# HandheldOsc.net
KiCad netlist of a schematic drawn in EAGLE
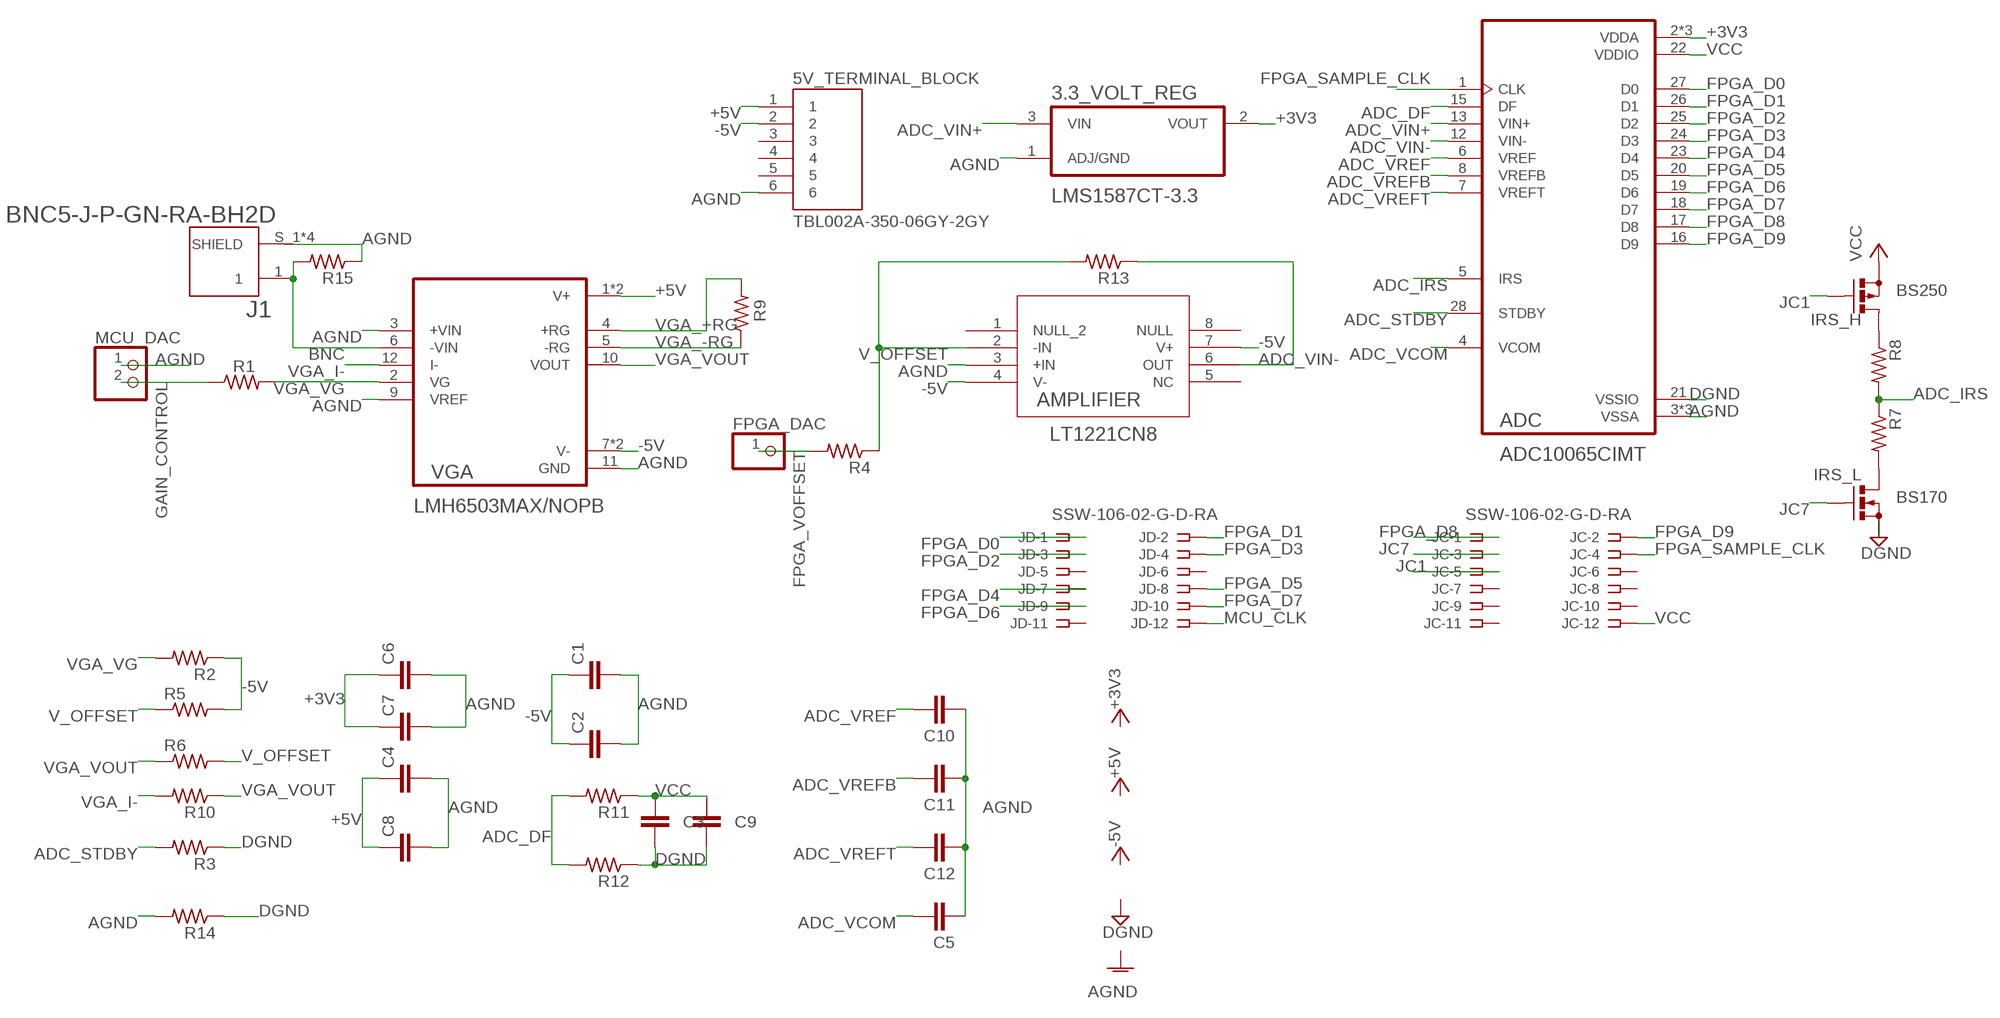
[diagram p0: schematic, sheet 1]

(export (version "E")
  (design (tool "Eeschema 10.0.6"))
  (components
    (comp (ref "3.3_VOLT_REG")
      (value "LMS1587CT-3.3")
      (footprint "eagle-import:TO254P1054X470X1955-3")
      (fields (field (name "MF") "Texas Instruments") (field (name "MP") "LMS1587CT-3.3/NOPB"))
      (libsource (lib "eagle-import") (part "LMS1587CT-3.3"))
    )
    (comp (ref "5V_TERMINAL_BLOCK")
      (value "TBL002A-350-06GY-2GY")
      (footprint "eagle-import:CUI_TBL002A-350-06GY-2GY")
      (fields (field (name "MF") "CUI Devices"))
      (libsource (lib "eagle-import") (part "TBL002A-350-06GY-2GY"))
    )
    (comp (ref "ADC")
      (value "ADC10065CIMT")
      (footprint "eagle-import:SOP65P640X120-28N")
      (fields (field (name "DIGI-KEY_PART_NUMBER") "296-35231-2-ND") (field (name "MF") "Texas Instruments"))
      (libsource (lib "eagle-import") (part "ADC10065CIMT"))
    )
    (comp (ref "AMPLIFIER")
      (value "LT1221CN8")
      (footprint "eagle-import:PDIP-8_N")
      (fields
        (field (name "DIGI-KEY_PART_NUMBER") "LT1221CN8#PBF-ND")
        (field (name "MF") "Linear Technology")
      )
      (libsource (lib "eagle-import") (part "LT1221CN8"))
    )
    (comp (ref "C1")
      (value "C2,5-3")
      (footprint "eagle-import:C2.5-3")
      (libsource (lib "eagle-import") (part "C2,5-3"))
    )
    (comp (ref "C2")
      (value "C2,5-3")
      (footprint "eagle-import:C2.5-3")
      (libsource (lib "eagle-import") (part "C2,5-3"))
    )
    (comp (ref "C3")
      (value "C2,5-3")
      (footprint "eagle-import:C2.5-3")
      (libsource (lib "eagle-import") (part "C2,5-3"))
    )
    (comp (ref "C4")
      (value "C2,5-3")
      (footprint "eagle-import:C2.5-3")
      (libsource (lib "eagle-import") (part "C2,5-3"))
    )
    (comp (ref "C5")
      (value "C2,5-3")
      (footprint "eagle-import:C2.5-3")
      (libsource (lib "eagle-import") (part "C2,5-3"))
    )
    (comp (ref "C6")
      (value "C2,5-3")
      (footprint "eagle-import:C2.5-3")
      (libsource (lib "eagle-import") (part "C2,5-3"))
    )
    (comp (ref "C7")
      (value "C2,5-3")
      (footprint "eagle-import:C2.5-3")
      (libsource (lib "eagle-import") (part "C2,5-3"))
    )
    (comp (ref "C8")
      (value "C2,5-3")
      (footprint "eagle-import:C2.5-3")
      (libsource (lib "eagle-import") (part "C2,5-3"))
    )
    (comp (ref "C9")
      (value "C2,5-3")
      (footprint "eagle-import:C2.5-3")
      (libsource (lib "eagle-import") (part "C2,5-3"))
    )
    (comp (ref "C10")
      (value "C2,5-3")
      (footprint "eagle-import:C2.5-3")
      (libsource (lib "eagle-import") (part "C2,5-3"))
    )
    (comp (ref "C11")
      (value "C2,5-3")
      (footprint "eagle-import:C2.5-3")
      (libsource (lib "eagle-import") (part "C2,5-3"))
    )
    (comp (ref "C12")
      (value "C2,5-3")
      (footprint "eagle-import:C2.5-3")
      (libsource (lib "eagle-import") (part "C2,5-3"))
    )
    (comp (ref "FPGA_DAC")
      (value "PINHD-1X1")
      (footprint "eagle-import:1X01")
      (libsource (lib "eagle-import") (part "PINHD-1X1"))
    )
    (comp (ref "IRS_H")
      (value "BS250")
      (footprint "eagle-import:SOT54E")
      (libsource (lib "eagle-import") (part "BS250"))
    )
    (comp (ref "IRS_L")
      (value "BS170")
      (footprint "eagle-import:SOT54E")
      (libsource (lib "eagle-import") (part "BS170"))
    )
    (comp (ref "J1")
      (value "BNC5-J-P-GN-RA-BH2D")
      (footprint "eagle-import:SAMTEC_BNC5-J-P-GN-RA-BH2D")
      (fields (field (name "DIGI-KEY_PART_NUMBER") "SAM9177-ND") (field (name "MF") "Samtec"))
      (libsource (lib "eagle-import") (part "BNC5-J-P-GN-RA-BH2D"))
    )
    (comp (ref "JC")
      (value "SSW-106-02-G-D-RA")
      (footprint "eagle-import:SSW-106-02-G-D-RA")
      (fields (field (name "MF") "Samtec Inc."))
      (libsource (lib "eagle-import") (part "SSW-106-02-G-D-RA"))
    )
    (comp (ref "JD")
      (value "SSW-106-02-G-D-RA")
      (footprint "eagle-import:SSW-106-02-G-D-RA")
      (fields (field (name "MF") "Samtec Inc."))
      (libsource (lib "eagle-import") (part "SSW-106-02-G-D-RA"))
    )
    (comp (ref "MCU_DAC")
      (value "PINHD-1X2")
      (footprint "eagle-import:1X02")
      (libsource (lib "eagle-import") (part "PINHD-1X2"))
    )
    (comp (ref "R1")
      (value "R-US_0207/12")
      (footprint "eagle-import:0207_12")
      (libsource (lib "eagle-import") (part "R-US_0207/12"))
    )
    (comp (ref "R2")
      (value "R-US_0207/12")
      (footprint "eagle-import:0207_12")
      (libsource (lib "eagle-import") (part "R-US_0207/12"))
    )
    (comp (ref "R3")
      (value "R-US_0207/12")
      (footprint "eagle-import:0207_12")
      (libsource (lib "eagle-import") (part "R-US_0207/12"))
    )
    (comp (ref "R4")
      (value "R-US_0207/12")
      (footprint "eagle-import:0207_12")
      (libsource (lib "eagle-import") (part "R-US_0207/12"))
    )
    (comp (ref "R5")
      (value "R-US_0207/12")
      (footprint "eagle-import:0207_12")
      (libsource (lib "eagle-import") (part "R-US_0207/12"))
    )
    (comp (ref "R6")
      (value "R-US_0207/12")
      (footprint "eagle-import:0207_12")
      (libsource (lib "eagle-import") (part "R-US_0207/12"))
    )
    (comp (ref "R7")
      (value "R-US_0207/12")
      (footprint "eagle-import:0207_12")
      (libsource (lib "eagle-import") (part "R-US_0207/12"))
    )
    (comp (ref "R8")
      (value "R-US_0207/12")
      (footprint "eagle-import:0207_12")
      (libsource (lib "eagle-import") (part "R-US_0207/12"))
    )
    (comp (ref "R9")
      (value "R-US_0207/12")
      (footprint "eagle-import:0207_12")
      (libsource (lib "eagle-import") (part "R-US_0207/12"))
    )
    (comp (ref "R10")
      (value "R-US_0207/12")
      (footprint "eagle-import:0207_12")
      (libsource (lib "eagle-import") (part "R-US_0207/12"))
    )
    (comp (ref "R11")
      (value "R-US_0207/12")
      (footprint "eagle-import:0207_12")
      (libsource (lib "eagle-import") (part "R-US_0207/12"))
    )
    (comp (ref "R12")
      (value "R-US_0207/12")
      (footprint "eagle-import:0207_12")
      (libsource (lib "eagle-import") (part "R-US_0207/12"))
    )
    (comp (ref "R13")
      (value "R-US_0207/12")
      (footprint "eagle-import:0207_12")
      (libsource (lib "eagle-import") (part "R-US_0207/12"))
    )
    (comp (ref "R14")
      (value "R-US_0207/12")
      (footprint "eagle-import:0207_12")
      (libsource (lib "eagle-import") (part "R-US_0207/12"))
    )
    (comp (ref "R15")
      (value "R-US_0207/12")
      (footprint "eagle-import:0207_12")
      (libsource (lib "eagle-import") (part "R-US_0207/12"))
    )
    (comp (ref "VGA")
      (value "LMH6503MAX/NOPB")
      (footprint "eagle-import:SOIC127P600X175-14N")
      (fields (field (name "DIGI-KEY_PART_NUMBER") "296-35331-1-ND") (field (name "MF") "Texas Instruments"))
      (libsource (lib "eagle-import") (part "LMH6503MAX/NOPB"))
    )
  )
  (nets
    (net (code "1") (name "+3V3") (class "Default")
      (node (ref "3.3_VOLT_REG") (pin "2") (pinfunction "VOUT_2") (pintype "output"))
      (node (ref "ADC") (pin "10") (pinfunction "VDDA_10") (pintype "power_in"))
      (node (ref "ADC") (pin "2") (pinfunction "VDDA_2") (pintype "power_in"))
      (node (ref "ADC") (pin "9") (pinfunction "VDDA_9") (pintype "power_in"))
      (node (ref "C6") (pin "1") (pinfunction "1_1") (pintype "passive"))
      (node (ref "C7") (pin "1") (pinfunction "1_1") (pintype "passive"))
    )
    (net (code "2") (name "+5V") (class "Default")
      (node (ref "5V_TERMINAL_BLOCK") (pin "1") (pinfunction "1_1") (pintype "passive"))
      (node (ref "C4") (pin "1") (pinfunction "1_1") (pintype "passive"))
      (node (ref "C8") (pin "1") (pinfunction "1_1") (pintype "passive"))
      (node (ref "VGA") (pin "1") (pinfunction "V+_1") (pintype "power_in"))
      (node (ref "VGA") (pin "14") (pinfunction "V+_14") (pintype "power_in"))
    )
    (net (code "3") (name "-5V") (class "Default")
      (node (ref "5V_TERMINAL_BLOCK") (pin "2") (pinfunction "2_2") (pintype "passive"))
      (node (ref "AMPLIFIER") (pin "4") (pinfunction "V-_4") (pintype "power_in"))
      (node (ref "AMPLIFIER") (pin "7") (pinfunction "V+_7") (pintype "power_in"))
      (node (ref "C1") (pin "1") (pinfunction "1_1") (pintype "passive"))
      (node (ref "C2") (pin "1") (pinfunction "1_1") (pintype "passive"))
      (node (ref "R2") (pin "1") (pinfunction "1_1") (pintype "passive"))
      (node (ref "R5") (pin "2") (pinfunction "2_2") (pintype "passive"))
      (node (ref "VGA") (pin "7") (pinfunction "V-_7") (pintype "power_in"))
      (node (ref "VGA") (pin "8") (pinfunction "V-_8") (pintype "power_in"))
    )
    (net (code "4") (name "/ADC_DF") (class "Default")
      (node (ref "ADC") (pin "15") (pinfunction "DF_15") (pintype "input"))
      (node (ref "R11") (pin "2") (pinfunction "2_2") (pintype "passive"))
      (node (ref "R12") (pin "2") (pinfunction "2_2") (pintype "passive"))
    )
    (net (code "5") (name "/ADC_IRS") (class "Default")
      (node (ref "ADC") (pin "5") (pinfunction "IRS_5") (pintype "bidirectional"))
      (node (ref "R7") (pin "1") (pinfunction "1_1") (pintype "passive"))
      (node (ref "R8") (pin "2") (pinfunction "2_2") (pintype "passive"))
    )
    (net (code "6") (name "/ADC_STDBY") (class "Default")
      (node (ref "ADC") (pin "28") (pinfunction "STDBY_28") (pintype "bidirectional"))
      (node (ref "R3") (pin "2") (pinfunction "2_2") (pintype "passive"))
    )
    (net (code "7") (name "/ADC_VCOM") (class "Default")
      (node (ref "ADC") (pin "4") (pinfunction "VCOM_4") (pintype "bidirectional"))
      (node (ref "C5") (pin "1") (pinfunction "1_1") (pintype "passive"))
    )
    (net (code "8") (name "/ADC_VIN+") (class "Default")
      (node (ref "3.3_VOLT_REG") (pin "3") (pinfunction "VIN_3") (pintype "input"))
      (node (ref "ADC") (pin "13") (pinfunction "VIN+_13") (pintype "input"))
    )
    (net (code "9") (name "/ADC_VIN-") (class "Default")
      (node (ref "ADC") (pin "12") (pinfunction "VIN-_12") (pintype "input"))
      (node (ref "AMPLIFIER") (pin "6") (pinfunction "OUT_6") (pintype "output"))
      (node (ref "R13") (pin "1") (pinfunction "1_1") (pintype "passive"))
    )
    (net (code "10") (name "/ADC_VREF") (class "Default")
      (node (ref "ADC") (pin "6") (pinfunction "VREF_6") (pintype "input"))
      (node (ref "C10") (pin "1") (pinfunction "1_1") (pintype "passive"))
    )
    (net (code "11") (name "/ADC_VREFB") (class "Default")
      (node (ref "ADC") (pin "8") (pinfunction "VREFB_8") (pintype "input"))
      (node (ref "C11") (pin "1") (pinfunction "1_1") (pintype "passive"))
    )
    (net (code "12") (name "/ADC_VREFT") (class "Default")
      (node (ref "ADC") (pin "7") (pinfunction "VREFT_7") (pintype "input"))
      (node (ref "C12") (pin "1") (pinfunction "1_1") (pintype "passive"))
    )
    (net (code "13") (name "/BNC") (class "Default")
      (node (ref "J1") (pin "1") (pinfunction "1_1") (pintype "passive"))
      (node (ref "R15") (pin "2") (pinfunction "2_2") (pintype "passive"))
      (node (ref "VGA") (pin "6") (pinfunction "-VIN_6") (pintype "input"))
    )
    (net (code "14") (name "/FPGA_D0") (class "Default")
      (node (ref "ADC") (pin "27") (pinfunction "D0_27") (pintype "output"))
      (node (ref "JD") (pin "1") (pinfunction "1_1") (pintype "passive"))
    )
    (net (code "15") (name "/FPGA_D1") (class "Default")
      (node (ref "ADC") (pin "26") (pinfunction "D1_26") (pintype "output"))
      (node (ref "JD") (pin "2") (pinfunction "1_2") (pintype "passive"))
    )
    (net (code "16") (name "/FPGA_D2") (class "Default")
      (node (ref "ADC") (pin "25") (pinfunction "D2_25") (pintype "output"))
      (node (ref "JD") (pin "3") (pinfunction "1_3") (pintype "passive"))
    )
    (net (code "17") (name "/FPGA_D3") (class "Default")
      (node (ref "ADC") (pin "24") (pinfunction "D3_24") (pintype "output"))
      (node (ref "JD") (pin "4") (pinfunction "1_4") (pintype "passive"))
    )
    (net (code "18") (name "/FPGA_D4") (class "Default")
      (node (ref "ADC") (pin "23") (pinfunction "D4_23") (pintype "output"))
      (node (ref "JD") (pin "7") (pinfunction "1_7") (pintype "passive"))
    )
    (net (code "19") (name "/FPGA_D5") (class "Default")
      (node (ref "ADC") (pin "20") (pinfunction "D5_20") (pintype "output"))
      (node (ref "JD") (pin "8") (pinfunction "1_8") (pintype "passive"))
    )
    (net (code "20") (name "/FPGA_D6") (class "Default")
      (node (ref "ADC") (pin "19") (pinfunction "D6_19") (pintype "output"))
      (node (ref "JD") (pin "9") (pinfunction "1_9") (pintype "passive"))
    )
    (net (code "21") (name "/FPGA_D7") (class "Default")
      (node (ref "ADC") (pin "18") (pinfunction "D7_18") (pintype "output"))
      (node (ref "JD") (pin "10") (pinfunction "1_10") (pintype "passive"))
    )
    (net (code "22") (name "/FPGA_D8") (class "Default")
      (node (ref "ADC") (pin "17") (pinfunction "D8_17") (pintype "output"))
      (node (ref "JC") (pin "1") (pinfunction "1_1") (pintype "passive"))
    )
    (net (code "23") (name "/FPGA_D9") (class "Default")
      (node (ref "ADC") (pin "16") (pinfunction "D9_16") (pintype "output"))
      (node (ref "JC") (pin "2") (pinfunction "1_2") (pintype "passive"))
    )
    (net (code "24") (name "/FPGA_SAMPLE_CLK") (class "Default")
      (node (ref "ADC") (pin "1") (pinfunction "CLK_1") (pintype "input"))
      (node (ref "JC") (pin "4") (pinfunction "1_4") (pintype "passive"))
    )
    (net (code "25") (name "/FPGA_VOFFSET") (class "Default")
      (node (ref "FPGA_DAC") (pin "1") (pinfunction "1_1") (pintype "passive"))
      (node (ref "R4") (pin "2") (pinfunction "2_2") (pintype "passive"))
    )
    (net (code "26") (name "/GAIN_CONTROL") (class "Default")
      (node (ref "MCU_DAC") (pin "2") (pinfunction "2_2") (pintype "passive"))
      (node (ref "R1") (pin "1") (pinfunction "1_1") (pintype "passive"))
    )
    (net (code "27") (name "/JC1") (class "Default")
      (node (ref "IRS_H") (pin "G") (pinfunction "G_G") (pintype "passive"))
      (node (ref "JC") (pin "5") (pinfunction "1_5") (pintype "passive"))
    )
    (net (code "28") (name "/JC7") (class "Default")
      (node (ref "IRS_L") (pin "G") (pinfunction "G_G") (pintype "passive"))
      (node (ref "JC") (pin "3") (pinfunction "1_3") (pintype "passive"))
    )
    (net (code "29") (name "/MCU_CLK") (class "Default")
      (node (ref "JD") (pin "12") (pinfunction "1_12") (pintype "passive"))
    )
    (net (code "30") (name "/VGA_+RG") (class "Default")
      (node (ref "R9") (pin "2") (pinfunction "2_2") (pintype "passive"))
      (node (ref "VGA") (pin "4") (pinfunction "+RG_4") (pintype "output"))
    )
    (net (code "31") (name "/VGA_-RG") (class "Default")
      (node (ref "R9") (pin "1") (pinfunction "1_1") (pintype "passive"))
      (node (ref "VGA") (pin "5") (pinfunction "-RG_5") (pintype "output"))
    )
    (net (code "32") (name "/VGA_I-") (class "Default")
      (node (ref "R10") (pin "2") (pinfunction "2_2") (pintype "passive"))
      (node (ref "VGA") (pin "12") (pinfunction "I-_12") (pintype "input"))
    )
    (net (code "33") (name "/VGA_VG") (class "Default")
      (node (ref "R1") (pin "2") (pinfunction "2_2") (pintype "passive"))
      (node (ref "R2") (pin "2") (pinfunction "2_2") (pintype "passive"))
      (node (ref "VGA") (pin "2") (pinfunction "VG_2") (pintype "input"))
    )
    (net (code "34") (name "/VGA_VOUT") (class "Default")
      (node (ref "R10") (pin "1") (pinfunction "1_1") (pintype "passive"))
      (node (ref "R6") (pin "1") (pinfunction "1_1") (pintype "passive"))
      (node (ref "VGA") (pin "10") (pinfunction "VOUT_10") (pintype "output"))
    )
    (net (code "35") (name "/V_OFFSET") (class "Default")
      (node (ref "AMPLIFIER") (pin "2") (pinfunction "-IN_2") (pintype "input"))
      (node (ref "R13") (pin "2") (pinfunction "2_2") (pintype "passive"))
      (node (ref "R4") (pin "1") (pinfunction "1_1") (pintype "passive"))
      (node (ref "R5") (pin "1") (pinfunction "1_1") (pintype "passive"))
      (node (ref "R6") (pin "2") (pinfunction "2_2") (pintype "passive"))
    )
    (net (code "36") (name "AGND") (class "Default")
      (node (ref "3.3_VOLT_REG") (pin "1") (pinfunction "ADJ/GND_1") (pintype "bidirectional"))
      (node (ref "5V_TERMINAL_BLOCK") (pin "6") (pinfunction "6_6") (pintype "passive"))
      (node (ref "ADC") (pin "11") (pinfunction "VSSA_11") (pintype "power_in"))
      (node (ref "ADC") (pin "14") (pinfunction "VSSA_14") (pintype "power_in"))
      (node (ref "ADC") (pin "3") (pinfunction "VSSA_3") (pintype "power_in"))
      (node (ref "AMPLIFIER") (pin "3") (pinfunction "+IN_3") (pintype "input"))
      (node (ref "C1") (pin "2") (pinfunction "2_2") (pintype "passive"))
      (node (ref "C10") (pin "2") (pinfunction "2_2") (pintype "passive"))
      (node (ref "C11") (pin "2") (pinfunction "2_2") (pintype "passive"))
      (node (ref "C12") (pin "2") (pinfunction "2_2") (pintype "passive"))
      (node (ref "C2") (pin "2") (pinfunction "2_2") (pintype "passive"))
      (node (ref "C4") (pin "2") (pinfunction "2_2") (pintype "passive"))
      (node (ref "C5") (pin "2") (pinfunction "2_2") (pintype "passive"))
      (node (ref "C6") (pin "2") (pinfunction "2_2") (pintype "passive"))
      (node (ref "C7") (pin "2") (pinfunction "2_2") (pintype "passive"))
      (node (ref "C8") (pin "2") (pinfunction "2_2") (pintype "passive"))
      (node (ref "J1") (pin "S_1") (pinfunction "SHIELD_S_1") (pintype "passive"))
      (node (ref "J1") (pin "S_2") (pinfunction "SHIELD_S_2") (pintype "passive"))
      (node (ref "J1") (pin "S_3") (pinfunction "SHIELD_S_3") (pintype "passive"))
      (node (ref "J1") (pin "S_4") (pinfunction "SHIELD_S_4") (pintype "passive"))
      (node (ref "MCU_DAC") (pin "1") (pinfunction "1_1") (pintype "passive"))
      (node (ref "R14") (pin "2") (pinfunction "2_2") (pintype "passive"))
      (node (ref "R15") (pin "1") (pinfunction "1_1") (pintype "passive"))
      (node (ref "VGA") (pin "11") (pinfunction "GND_11") (pintype "power_in"))
      (node (ref "VGA") (pin "3") (pinfunction "+VIN_3") (pintype "input"))
      (node (ref "VGA") (pin "9") (pinfunction "VREF_9") (pintype "input"))
    )
    (net (code "37") (name "DGND") (class "Default")
      (node (ref "ADC") (pin "21") (pinfunction "VSSIO_21") (pintype "power_in"))
      (node (ref "C3") (pin "2") (pinfunction "2_2") (pintype "passive"))
      (node (ref "C9") (pin "2") (pinfunction "2_2") (pintype "passive"))
      (node (ref "IRS_L") (pin "S") (pinfunction "S_S") (pintype "passive"))
      (node (ref "R12") (pin "1") (pinfunction "1_1") (pintype "passive"))
      (node (ref "R14") (pin "1") (pinfunction "1_1") (pintype "passive"))
      (node (ref "R3") (pin "1") (pinfunction "1_1") (pintype "passive"))
    )
    (net (code "38") (name "Net-(IRS_H-PadD)") (class "Default")
      (node (ref "IRS_H") (pin "D") (pinfunction "D_D") (pintype "passive"))
      (node (ref "R8") (pin "1") (pinfunction "1_1") (pintype "passive"))
    )
    (net (code "39") (name "Net-(IRS_L-PadD)") (class "Default")
      (node (ref "IRS_L") (pin "D") (pinfunction "D_D") (pintype "passive"))
      (node (ref "R7") (pin "2") (pinfunction "2_2") (pintype "passive"))
    )
    (net (code "40") (name "VCC") (class "Default")
      (node (ref "ADC") (pin "22") (pinfunction "VDDIO_22") (pintype "power_in"))
      (node (ref "C3") (pin "1") (pinfunction "1_1") (pintype "passive"))
      (node (ref "C9") (pin "1") (pinfunction "1_1") (pintype "passive"))
      (node (ref "IRS_H") (pin "S") (pinfunction "S_S") (pintype "passive"))
      (node (ref "JC") (pin "12") (pinfunction "1_12") (pintype "passive"))
      (node (ref "R11") (pin "1") (pinfunction "1_1") (pintype "passive"))
    )
    (net (code "41") (name "unconnected-(5V_TERMINAL_BLOCK-Pad3)") (class "Default")
      (node (ref "5V_TERMINAL_BLOCK") (pin "3") (pinfunction "3_3") (pintype "passive"))
    )
    (net (code "42") (name "unconnected-(5V_TERMINAL_BLOCK-Pad4)") (class "Default")
      (node (ref "5V_TERMINAL_BLOCK") (pin "4") (pinfunction "4_4") (pintype "passive"))
    )
    (net (code "43") (name "unconnected-(5V_TERMINAL_BLOCK-Pad5)") (class "Default")
      (node (ref "5V_TERMINAL_BLOCK") (pin "5") (pinfunction "5_5") (pintype "passive"))
    )
    (net (code "44") (name "unconnected-(AMPLIFIER-NC-Pad5)") (class "Default")
      (node (ref "AMPLIFIER") (pin "5") (pinfunction "NC_5") (pintype "passive"))
    )
    (net (code "45") (name "unconnected-(AMPLIFIER-NULL-Pad8)") (class "Default")
      (node (ref "AMPLIFIER") (pin "8") (pinfunction "NULL_8") (pintype "passive"))
    )
    (net (code "46") (name "unconnected-(AMPLIFIER-NULL_2-Pad1)") (class "Default")
      (node (ref "AMPLIFIER") (pin "1") (pinfunction "NULL_2_1") (pintype "passive"))
    )
    (net (code "47") (name "unconnected-(JCB-1-Pad10)") (class "Default")
      (node (ref "JC") (pin "10") (pinfunction "1_10") (pintype "passive"))
    )
    (net (code "48") (name "unconnected-(JCC-1-Pad11)") (class "Default")
      (node (ref "JC") (pin "11") (pinfunction "1_11") (pintype "passive"))
    )
    (net (code "49") (name "unconnected-(JCI-1-Pad6)") (class "Default")
      (node (ref "JC") (pin "6") (pinfunction "1_6") (pintype "passive"))
    )
    (net (code "50") (name "unconnected-(JCJ-1-Pad7)") (class "Default")
      (node (ref "JC") (pin "7") (pinfunction "1_7") (pintype "passive"))
    )
    (net (code "51") (name "unconnected-(JCK-1-Pad8)") (class "Default")
      (node (ref "JC") (pin "8") (pinfunction "1_8") (pintype "passive"))
    )
    (net (code "52") (name "unconnected-(JCL-1-Pad9)") (class "Default")
      (node (ref "JC") (pin "9") (pinfunction "1_9") (pintype "passive"))
    )
    (net (code "53") (name "unconnected-(JDC-1-Pad11)") (class "Default")
      (node (ref "JD") (pin "11") (pinfunction "1_11") (pintype "passive"))
    )
    (net (code "54") (name "unconnected-(JDH-1-Pad5)") (class "Default")
      (node (ref "JD") (pin "5") (pinfunction "1_5") (pintype "passive"))
    )
    (net (code "55") (name "unconnected-(JDI-1-Pad6)") (class "Default")
      (node (ref "JD") (pin "6") (pinfunction "1_6") (pintype "passive"))
    )
  )
)
